# CH340N.net
KiCad netlist of a schematic drawn in Altium Designer
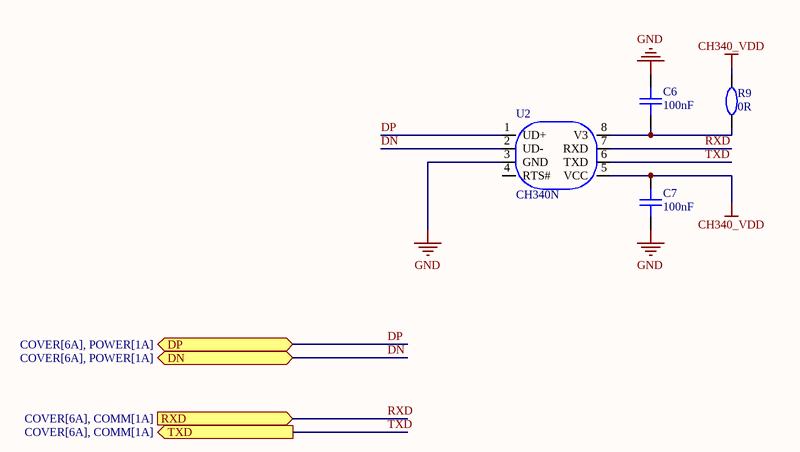
[diagram p0: CH340N.SchDoc]

(export (version "E")
  (design (tool "Eeschema 10.0.6"))
  (components
    (comp (ref "C6")
      (value "100nF")
      (footprint "C0402")
      (fields (field (name "NAME") "100nF"))
      (libsource (lib "my_library") (part "CAP_0402"))
    )
    (comp (ref "C7")
      (value "100nF")
      (footprint "C0402")
      (fields (field (name "NAME") "100nF"))
      (libsource (lib "my_library") (part "CAP_0402"))
    )
    (comp (ref "R9")
      (value "0R")
      (footprint "R0402")
      (fields (field (name "NAME") "0R"))
      (libsource (lib "my_library") (part "Res_0402"))
    )
    (comp (ref "U2")
      (value "CH340N")
      (footprint "SOP-8_L4.9-W3.9-P1.27-LS6.0-BL")
      (fields (field (name "MANUFACTURER") "WCH(南京沁恒)") (field (name "NAME") "CH340N"))
      (libsource (lib "my_library") (part "CH340N"))
    )
  )
  (nets
    (net (code "1") (name "/DN") (class "Default")
      (node (ref "U2") (pin "2") (pinfunction "UD-_2") (pintype "passive"))
    )
    (net (code "2") (name "/DP") (class "Default")
      (node (ref "U2") (pin "1") (pinfunction "UD+_1") (pintype "passive"))
    )
    (net (code "3") (name "/RXD") (class "Default")
      (node (ref "U2") (pin "7") (pinfunction "RXD_7") (pintype "passive"))
    )
    (net (code "4") (name "/TXD") (class "Default")
      (node (ref "U2") (pin "6") (pinfunction "TXD_6") (pintype "passive"))
    )
    (net (code "5") (name "CH340_VDD") (class "Default")
      (node (ref "C7") (pin "2") (pinfunction "2_2") (pintype "passive"))
      (node (ref "R9") (pin "2") (pinfunction "2_2") (pintype "passive"))
      (node (ref "U2") (pin "5") (pinfunction "VCC_5") (pintype "passive"))
    )
    (net (code "6") (name "GND") (class "Default")
      (node (ref "C6") (pin "2") (pinfunction "2_2") (pintype "passive"))
      (node (ref "C7") (pin "1") (pinfunction "1_1") (pintype "passive"))
      (node (ref "U2") (pin "3") (pinfunction "GND_3") (pintype "passive"))
    )
    (net (code "7") (name "Net-(U2-V3)") (class "Default")
      (node (ref "C6") (pin "1") (pinfunction "1_1") (pintype "passive"))
      (node (ref "R9") (pin "1") (pinfunction "1_1") (pintype "passive"))
      (node (ref "U2") (pin "8") (pinfunction "V3_8") (pintype "passive"))
    )
    (net (code "8") (name "unconnected-(U2-RTS#-Pad4)") (class "Default")
      (node (ref "U2") (pin "4") (pinfunction "RTS#_4") (pintype "passive"))
    )
  )
)
